# remap_2025-11-01.net
KiCad netlist of a schematic drawn in EasyEDA Pro
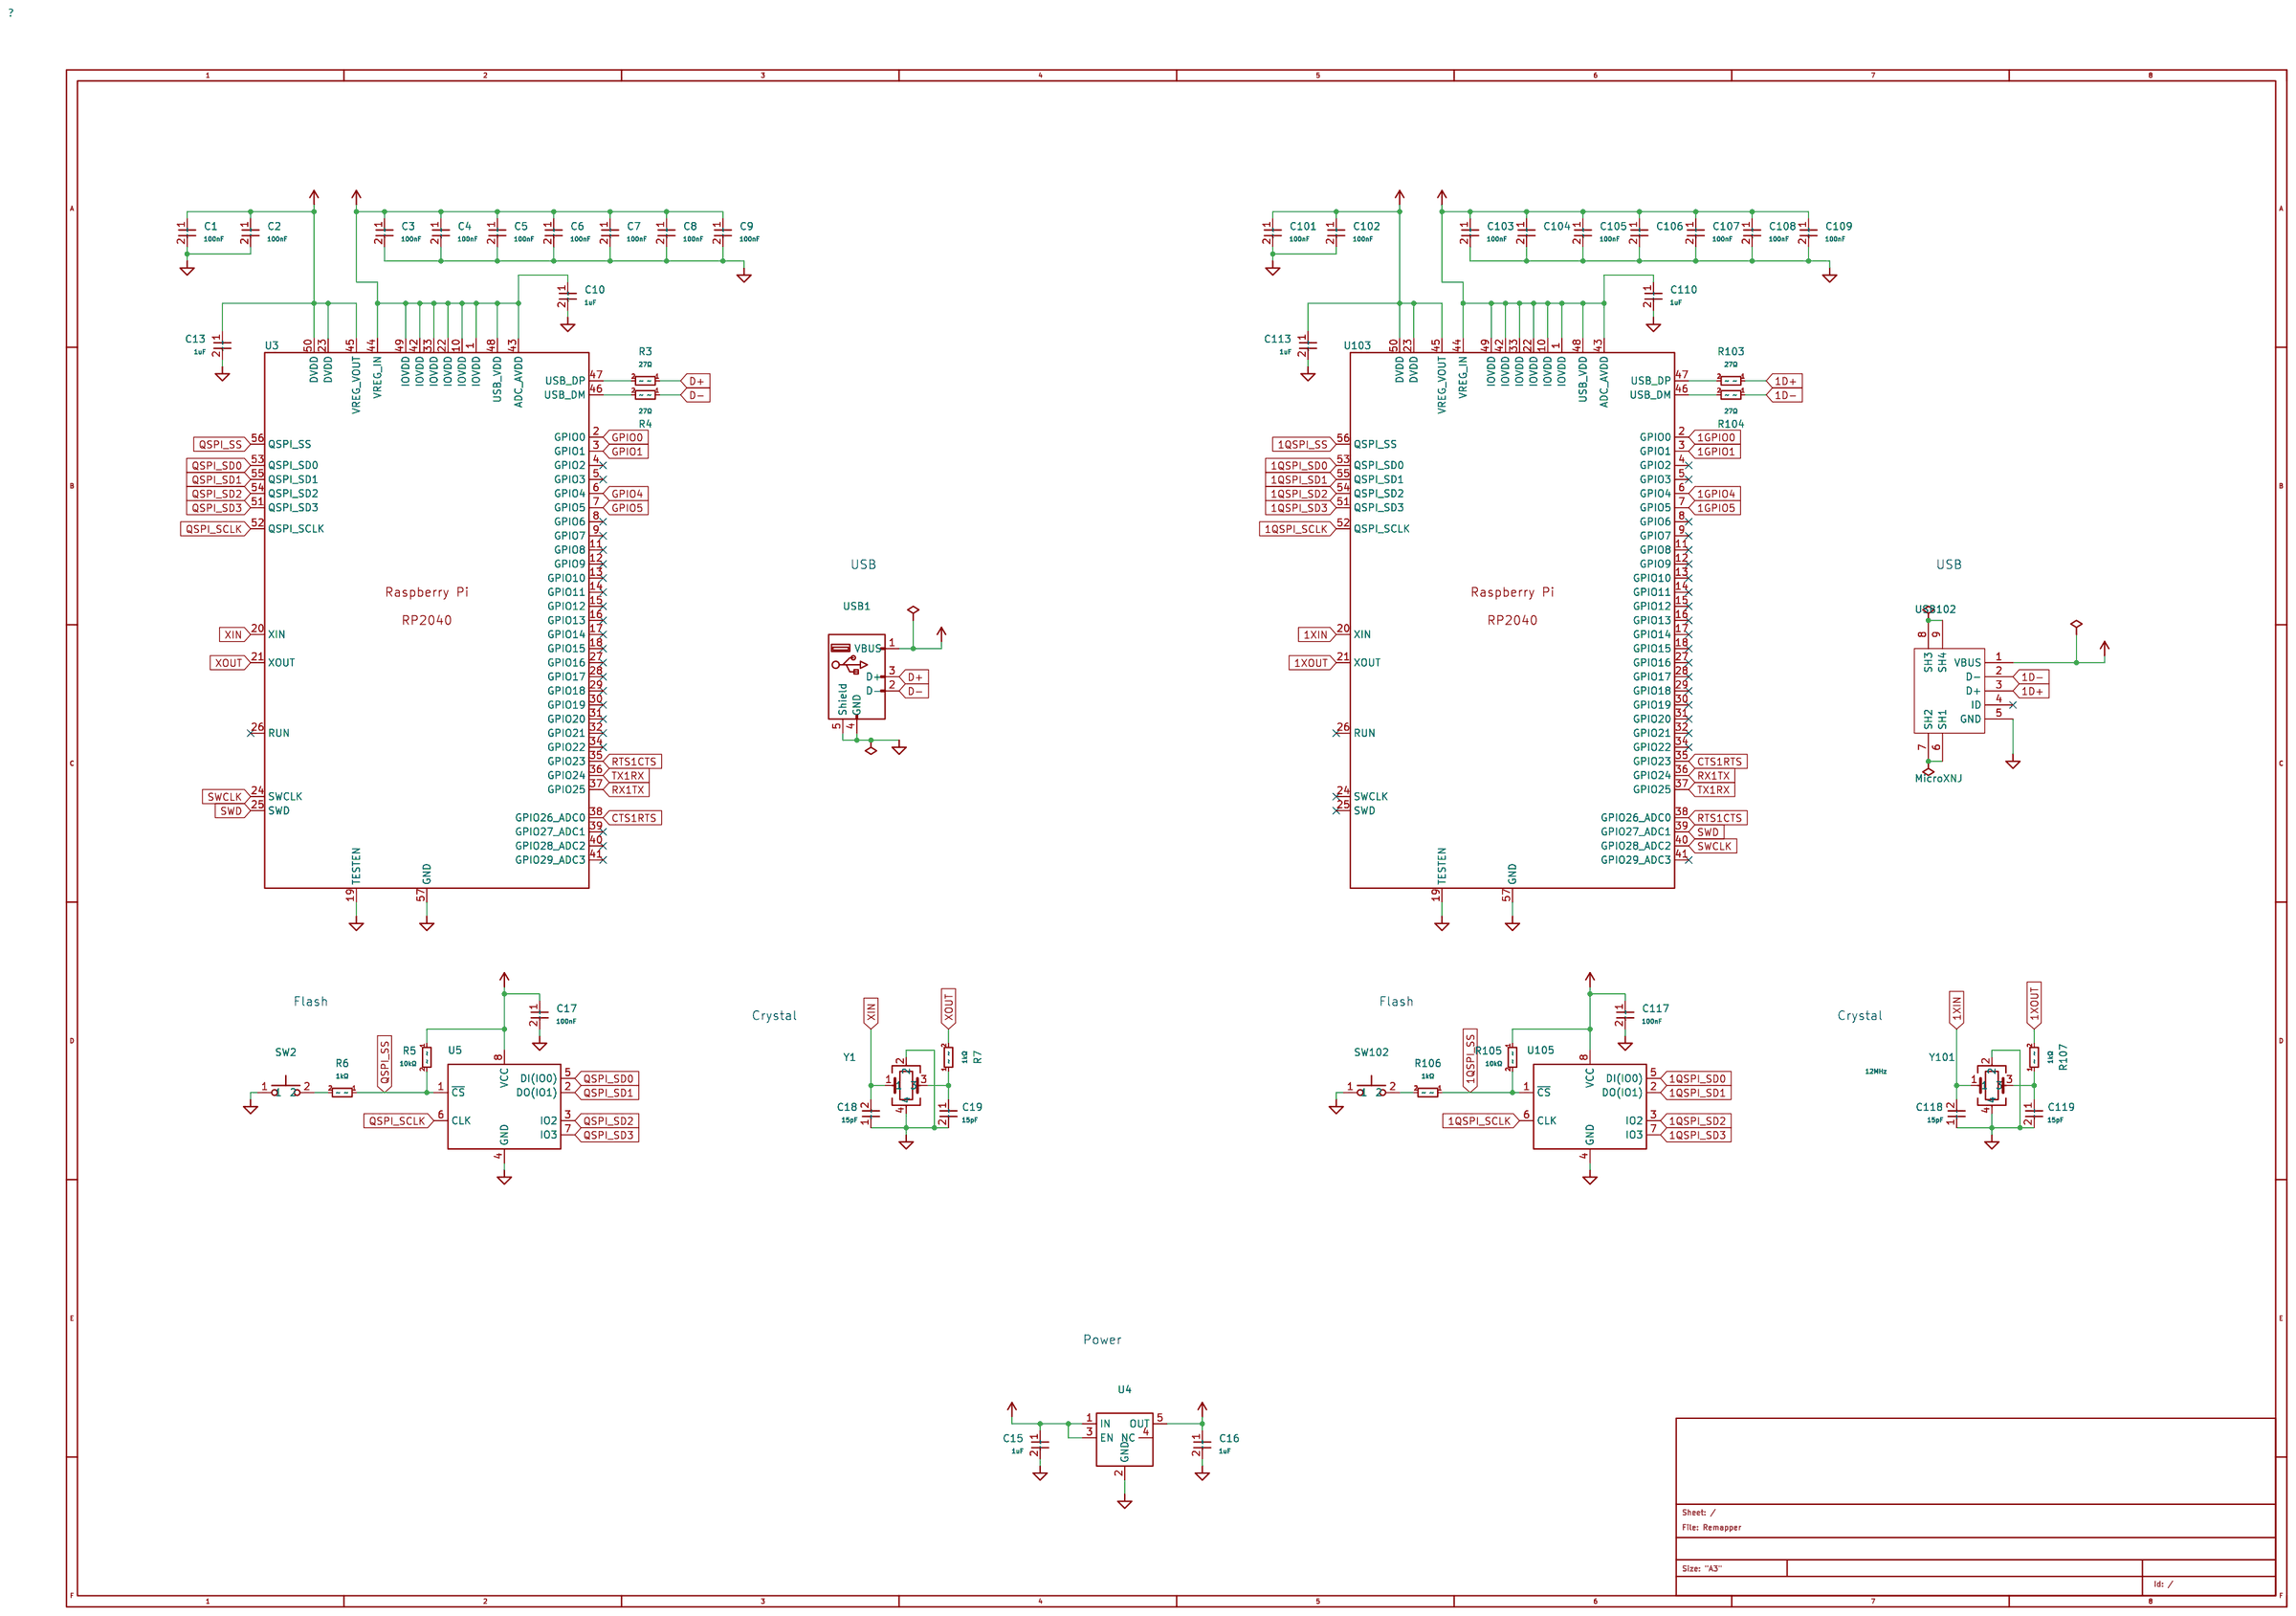
[diagram p0: schematic sheet]

(export (version "E")
  (design (tool "Eeschema 10.0.6"))
  (components
    (comp (ref "C1")
      (value "100nF")
      (description "Capacitance:100nF Tolerance:±10% Tolerance:±10% Voltage Rating:16V Temperature Coefficient:X7R")
      (fields
        (field (name "Manufacturer Part") "CL05B104KO5NNNC")
        (field (name "Manufacturer") "SAMSUNG(三星)")
      )
      (libsource (lib "easyedapro") (part "Device_C_Small"))
    )
    (comp (ref "C2")
      (value "100nF")
      (description "Capacitance:100nF Tolerance:±10% Tolerance:±10% Voltage Rating:16V Temperature Coefficient:X7R")
      (fields
        (field (name "Manufacturer Part") "CL05B104KO5NNNC")
        (field (name "Manufacturer") "SAMSUNG(三星)")
      )
      (libsource (lib "easyedapro") (part "Device_C_Small"))
    )
    (comp (ref "C3")
      (value "100nF")
      (description "Capacitance:100nF Tolerance:±10% Tolerance:±10% Voltage Rating:16V Temperature Coefficient:X7R")
      (fields
        (field (name "Manufacturer Part") "CL05B104KO5NNNC")
        (field (name "Manufacturer") "SAMSUNG(三星)")
      )
      (libsource (lib "easyedapro") (part "Device_C_Small"))
    )
    (comp (ref "C4")
      (value "100nF")
      (description "Capacitance:100nF Tolerance:±10% Tolerance:±10% Voltage Rating:16V Temperature Coefficient:X7R")
      (fields
        (field (name "Manufacturer Part") "CL05B104KO5NNNC")
        (field (name "Manufacturer") "SAMSUNG(三星)")
      )
      (libsource (lib "easyedapro") (part "Device_C_Small"))
    )
    (comp (ref "C5")
      (value "100nF")
      (description "Capacitance:100nF Tolerance:±10% Tolerance:±10% Voltage Rating:16V Temperature Coefficient:X7R")
      (fields
        (field (name "Manufacturer Part") "CL05B104KO5NNNC")
        (field (name "Manufacturer") "SAMSUNG(三星)")
      )
      (libsource (lib "easyedapro") (part "Device_C_Small"))
    )
    (comp (ref "C6")
      (value "100nF")
      (description "Capacitance:100nF Tolerance:±10% Tolerance:±10% Voltage Rating:16V Temperature Coefficient:X7R")
      (fields
        (field (name "Manufacturer Part") "CL05B104KO5NNNC")
        (field (name "Manufacturer") "SAMSUNG(三星)")
      )
      (libsource (lib "easyedapro") (part "Device_C_Small"))
    )
    (comp (ref "C7")
      (value "100nF")
      (description "Capacitance:100nF Tolerance:±10% Tolerance:±10% Voltage Rating:16V Temperature Coefficient:X7R")
      (fields
        (field (name "Manufacturer Part") "CL05B104KO5NNNC")
        (field (name "Manufacturer") "SAMSUNG(三星)")
      )
      (libsource (lib "easyedapro") (part "Device_C_Small"))
    )
    (comp (ref "C8")
      (value "100nF")
      (description "Capacitance:100nF Tolerance:±10% Tolerance:±10% Voltage Rating:16V Temperature Coefficient:X7R")
      (fields
        (field (name "Manufacturer Part") "CL05B104KO5NNNC")
        (field (name "Manufacturer") "SAMSUNG(三星)")
      )
      (libsource (lib "easyedapro") (part "Device_C_Small"))
    )
    (comp (ref "C9")
      (value "100nF")
      (description "Capacitance:100nF Tolerance:±10% Tolerance:±10% Voltage Rating:16V Temperature Coefficient:X7R")
      (fields
        (field (name "Manufacturer Part") "CL05B104KO5NNNC")
        (field (name "Manufacturer") "SAMSUNG(三星)")
      )
      (libsource (lib "easyedapro") (part "Device_C_Small"))
    )
    (comp (ref "C10")
      (value "1uF")
      (description "Capacitance:1uF Tolerance:±10% Tolerance:±10% Voltage Rating:25V Temperature Coefficient:X5R")
      (fields
        (field (name "Manufacturer Part") "CL05A105KA5NQNC")
        (field (name "Manufacturer") "SAMSUNG(三星)")
      )
      (libsource (lib "easyedapro") (part "Device_C_Small"))
    )
    (comp (ref "C13")
      (value "1uF")
      (description "Capacitance:1uF Tolerance:±10% Tolerance:±10% Voltage Rating:25V Temperature Coefficient:X5R")
      (fields
        (field (name "Manufacturer Part") "CL05A105KA5NQNC")
        (field (name "Manufacturer") "SAMSUNG(三星)")
      )
      (libsource (lib "easyedapro") (part "Device_C_Small"))
    )
    (comp (ref "C15")
      (value "1uF")
      (description "Capacitance:1uF Tolerance:±10% Tolerance:±10% Voltage Rating:25V Temperature Coefficient:X5R")
      (fields
        (field (name "Manufacturer Part") "CL05A105KA5NQNC")
        (field (name "Manufacturer") "SAMSUNG(三星)")
      )
      (libsource (lib "easyedapro") (part "Device_C_Small"))
    )
    (comp (ref "C16")
      (value "1uF")
      (description "Capacitance:1uF Tolerance:±10% Tolerance:±10% Voltage Rating:25V Temperature Coefficient:X5R")
      (fields
        (field (name "Manufacturer Part") "CL05A105KA5NQNC")
        (field (name "Manufacturer") "SAMSUNG(三星)")
      )
      (libsource (lib "easyedapro") (part "Device_C_Small"))
    )
    (comp (ref "C17")
      (value "100nF")
      (description "Capacitance:100nF Tolerance:±10% Tolerance:±10% Voltage Rating:16V Temperature Coefficient:X7R")
      (fields
        (field (name "Manufacturer Part") "CL05B104KO5NNNC")
        (field (name "Manufacturer") "SAMSUNG(三星)")
      )
      (libsource (lib "easyedapro") (part "Device_C_Small"))
    )
    (comp (ref "C18")
      (value "15pF")
      (description "Capacitance:15pF Tolerance:±5% Tolerance:±5% Voltage Rating:50V Temperature Coefficient:C0G")
      (fields (field (name "Manufacturer Part") "0402CG150J500NT") (field (name "Manufacturer") "FH(风华)"))
      (libsource (lib "easyedapro") (part "Device_C_Small"))
    )
    (comp (ref "C19")
      (value "15pF")
      (description "Capacitance:15pF Tolerance:±5% Tolerance:±5% Voltage Rating:50V Temperature Coefficient:C0G")
      (fields (field (name "Manufacturer Part") "0402CG150J500NT") (field (name "Manufacturer") "FH(风华)"))
      (libsource (lib "easyedapro") (part "Device_C_Small"))
    )
    (comp (ref "C101")
      (value "100nF")
      (description "Capacitance:100nF Tolerance:±10% Tolerance:±10% Voltage Rating:16V Temperature Coefficient:X7R")
      (fields
        (field (name "Manufacturer Part") "CL05B104KO5NNNC")
        (field (name "Manufacturer") "SAMSUNG(三星)")
      )
      (libsource (lib "easyedapro") (part "Device_C_Small"))
    )
    (comp (ref "C102")
      (value "100nF")
      (description "Capacitance:100nF Tolerance:±10% Tolerance:±10% Voltage Rating:16V Temperature Coefficient:X7R")
      (fields
        (field (name "Manufacturer Part") "CL05B104KO5NNNC")
        (field (name "Manufacturer") "SAMSUNG(三星)")
      )
      (libsource (lib "easyedapro") (part "Device_C_Small"))
    )
    (comp (ref "C103")
      (value "100nF")
      (description "Capacitance:100nF Tolerance:±10% Tolerance:±10% Voltage Rating:16V Temperature Coefficient:X7R")
      (fields
        (field (name "Manufacturer Part") "CL05B104KO5NNNC")
        (field (name "Manufacturer") "SAMSUNG(三星)")
      )
      (libsource (lib "easyedapro") (part "Device_C_Small"))
    )
    (comp (ref "C104")
      (value "100nF")
      (description "Capacitance:100nF Tolerance:±10% Tolerance:±10% Voltage Rating:16V Temperature Coefficient:X7R")
      (fields
        (field (name "Manufacturer Part") "CL05B104KO5NNNC")
        (field (name "Manufacturer") "SAMSUNG(三星)")
      )
      (libsource (lib "easyedapro") (part "Device_C_Small"))
    )
    (comp (ref "C105")
      (value "100nF")
      (description "Capacitance:100nF Tolerance:±10% Tolerance:±10% Voltage Rating:16V Temperature Coefficient:X7R")
      (fields
        (field (name "Manufacturer Part") "CL05B104KO5NNNC")
        (field (name "Manufacturer") "SAMSUNG(三星)")
      )
      (libsource (lib "easyedapro") (part "Device_C_Small"))
    )
    (comp (ref "C106")
      (value "100nF")
      (description "Capacitance:100nF Tolerance:±10% Tolerance:±10% Voltage Rating:16V Temperature Coefficient:X7R")
      (fields
        (field (name "Manufacturer Part") "CL05B104KO5NNNC")
        (field (name "Manufacturer") "SAMSUNG(三星)")
      )
      (libsource (lib "easyedapro") (part "Device_C_Small"))
    )
    (comp (ref "C107")
      (value "100nF")
      (description "Capacitance:100nF Tolerance:±10% Tolerance:±10% Voltage Rating:16V Temperature Coefficient:X7R")
      (fields
        (field (name "Manufacturer Part") "CL05B104KO5NNNC")
        (field (name "Manufacturer") "SAMSUNG(三星)")
      )
      (libsource (lib "easyedapro") (part "Device_C_Small"))
    )
    (comp (ref "C108")
      (value "100nF")
      (description "Capacitance:100nF Tolerance:±10% Tolerance:±10% Voltage Rating:16V Temperature Coefficient:X7R")
      (fields
        (field (name "Manufacturer Part") "CL05B104KO5NNNC")
        (field (name "Manufacturer") "SAMSUNG(三星)")
      )
      (libsource (lib "easyedapro") (part "Device_C_Small"))
    )
    (comp (ref "C109")
      (value "100nF")
      (description "Capacitance:100nF Tolerance:±10% Tolerance:±10% Voltage Rating:16V Temperature Coefficient:X7R")
      (fields
        (field (name "Manufacturer Part") "CL05B104KO5NNNC")
        (field (name "Manufacturer") "SAMSUNG(三星)")
      )
      (libsource (lib "easyedapro") (part "Device_C_Small"))
    )
    (comp (ref "C110")
      (value "1uF")
      (description "Capacitance:1uF Tolerance:±10% Tolerance:±10% Voltage Rating:25V Temperature Coefficient:X5R")
      (fields
        (field (name "Manufacturer Part") "CL05A105KA5NQNC")
        (field (name "Manufacturer") "SAMSUNG(三星)")
      )
      (libsource (lib "easyedapro") (part "Device_C_Small"))
    )
    (comp (ref "C113")
      (value "1uF")
      (description "Capacitance:1uF Tolerance:±10% Tolerance:±10% Voltage Rating:25V Temperature Coefficient:X5R")
      (fields
        (field (name "Manufacturer Part") "CL05A105KA5NQNC")
        (field (name "Manufacturer") "SAMSUNG(三星)")
      )
      (libsource (lib "easyedapro") (part "Device_C_Small"))
    )
    (comp (ref "C117")
      (value "100nF")
      (description "Capacitance:100nF Tolerance:±10% Tolerance:±10% Voltage Rating:16V Temperature Coefficient:X7R")
      (fields
        (field (name "Manufacturer Part") "CL05B104KO5NNNC")
        (field (name "Manufacturer") "SAMSUNG(三星)")
      )
      (libsource (lib "easyedapro") (part "Device_C_Small"))
    )
    (comp (ref "C118")
      (value "15pF")
      (description "Capacitance:15pF Tolerance:±5% Tolerance:±5% Voltage Rating:50V Temperature Coefficient:C0G")
      (fields (field (name "Manufacturer Part") "0402CG150J500NT") (field (name "Manufacturer") "FH(风华)"))
      (libsource (lib "easyedapro") (part "Device_C_Small"))
    )
    (comp (ref "C119")
      (value "15pF")
      (description "Capacitance:15pF Tolerance:±5% Tolerance:±5% Voltage Rating:50V Temperature Coefficient:C0G")
      (fields (field (name "Manufacturer Part") "0402CG150J500NT") (field (name "Manufacturer") "FH(风华)"))
      (libsource (lib "easyedapro") (part "Device_C_Small"))
    )
    (comp (ref "R3")
      (value "27Ω")
      (fields (field (name "Manufacturer Part") "RC0402FR-0727RL") (field (name "Manufacturer") "YAGEO(国巨)"))
      (libsource (lib "easyedapro") (part "Device_R_Small"))
    )
    (comp (ref "R4")
      (value "27Ω")
      (fields (field (name "Manufacturer Part") "RC0402FR-0727RL") (field (name "Manufacturer") "YAGEO(国巨)"))
      (libsource (lib "easyedapro") (part "Device_R_Small"))
    )
    (comp (ref "R5")
      (value "10kΩ")
      (fields
        (field (name "Manufacturer Part") "0402WGF1002TCE")
        (field (name "Manufacturer") "UNI-ROYAL(厚声)")
      )
      (libsource (lib "easyedapro") (part "Device_R_Small"))
    )
    (comp (ref "R6")
      (value "1kΩ")
      (fields
        (field (name "Manufacturer Part") "0402WGF1001TCE")
        (field (name "Manufacturer") "UNI-ROYAL(厚声)")
      )
      (libsource (lib "easyedapro") (part "Device_R_Small"))
    )
    (comp (ref "R7")
      (value "1kΩ")
      (fields
        (field (name "Manufacturer Part") "0402WGF1001TCE")
        (field (name "Manufacturer") "UNI-ROYAL(厚声)")
      )
      (libsource (lib "easyedapro") (part "Device_R_Small"))
    )
    (comp (ref "R103")
      (value "27Ω")
      (fields (field (name "Manufacturer Part") "RC0402FR-0727RL") (field (name "Manufacturer") "YAGEO(国巨)"))
      (libsource (lib "easyedapro") (part "Device_R_Small"))
    )
    (comp (ref "R104")
      (value "27Ω")
      (fields (field (name "Manufacturer Part") "RC0402FR-0727RL") (field (name "Manufacturer") "YAGEO(国巨)"))
      (libsource (lib "easyedapro") (part "Device_R_Small"))
    )
    (comp (ref "R105")
      (value "10kΩ")
      (fields
        (field (name "Manufacturer Part") "0402WGF1002TCE")
        (field (name "Manufacturer") "UNI-ROYAL(厚声)")
      )
      (libsource (lib "easyedapro") (part "Device_R_Small"))
    )
    (comp (ref "R106")
      (value "1kΩ")
      (fields
        (field (name "Manufacturer Part") "0402WGF1001TCE")
        (field (name "Manufacturer") "UNI-ROYAL(厚声)")
      )
      (libsource (lib "easyedapro") (part "Device_R_Small"))
    )
    (comp (ref "R107")
      (value "1kΩ")
      (fields
        (field (name "Manufacturer Part") "0402WGF1001TCE")
        (field (name "Manufacturer") "UNI-ROYAL(厚声)")
      )
      (libsource (lib "easyedapro") (part "Device_R_Small"))
    )
    (comp (ref "SW2")
      (value "B3U-1000P")
      (fields (field (name "Manufacturer") "OMRON(欧姆龙)"))
      (libsource (lib "easyedapro") (part "Switch_SW_Push"))
    )
    (comp (ref "SW102")
      (value "B3U-1000P")
      (fields (field (name "Manufacturer") "OMRON(欧姆龙)"))
      (libsource (lib "easyedapro") (part "Switch_SW_Push"))
    )
    (comp (ref "U3")
      (value "RP2040")
      (description "CPU Core:- CPU Maximum Speed:133MHz Number of I/O:30 ADC (Bit):12bit Applications:-")
      (fields (field (name "Manufacturer") "Raspberry Pi(树莓派)"))
      (libsource (lib "easyedapro") (part "RP2040_RP2040"))
    )
    (comp (ref "U4")
      (value "TLV73333PDBVR")
      (fields (field (name "Manufacturer") "TI(德州仪器)"))
      (libsource (lib "easyedapro") (part "Regulator_Linear_TLV73333PDBV"))
    )
    (comp (ref "U5")
      (value "W25Q16JVUXIQ")
      (fields (field (name "Manufacturer") "Winbond(华邦)"))
      (libsource (lib "easyedapro") (part "Memory_Flash_W25Q128JVS"))
    )
    (comp (ref "U103")
      (value "RP2040")
      (description "CPU Core:- CPU Maximum Speed:133MHz Number of I/O:30 ADC (Bit):12bit Applications:-")
      (fields (field (name "Manufacturer") "Raspberry Pi(树莓派)"))
      (libsource (lib "easyedapro") (part "RP2040_RP2040"))
    )
    (comp (ref "U105")
      (value "W25Q16JVUXIQ")
      (fields (field (name "Manufacturer") "Winbond(华邦)"))
      (libsource (lib "easyedapro") (part "Memory_Flash_W25Q128JVS"))
    )
    (comp (ref "USB1")
      (value "U-USBAR04P-F002")
      (fields (field (name "Manufacturer") "Ckmtw(灿科盟)"))
      (libsource (lib "easyedapro") (part "Connector_USB_A"))
    )
    (comp (ref "USB102")
      (value "MicroXNJ")
      (footprint "easyedapro:MICRO-USB-SMD_MICROXNJ")
      (fields (field (name "Manufacturer") "SHOU HAN(首韩)"))
      (libsource (lib "easyedapro") (part "MICROXNJ"))
    )
    (comp (ref "Y1")
      (value "12MHz")
      (fields (field (name "Manufacturer Part") "X252012MMB4SI-24") (field (name "Manufacturer") "YXC(扬兴晶振)"))
      (libsource (lib "easyedapro") (part "Device_Crystal_GND24"))
    )
    (comp (ref "Y101")
      (value "12MHz")
      (fields (field (name "Manufacturer Part") "X252012MMB4SI-24") (field (name "Manufacturer") "YXC(扬兴晶振)"))
      (libsource (lib "easyedapro") (part "Device_Crystal_GND24"))
    )
  )
  (nets
    (net (code "1") (name "+1V1") (class "Default")
      (node (ref "C1") (pin "1") (pinfunction "~_1") (pintype "unspecified"))
      (node (ref "C13") (pin "1") (pinfunction "~_1") (pintype "unspecified"))
      (node (ref "C2") (pin "1") (pinfunction "~_1") (pintype "unspecified"))
      (node (ref "U3") (pin "23") (pinfunction "DVDD_23") (pintype "unspecified"))
      (node (ref "U3") (pin "45") (pinfunction "VREG_VOUT_45") (pintype "unspecified"))
      (node (ref "U3") (pin "50") (pinfunction "DVDD_50") (pintype "unspecified"))
    )
    (net (code "2") (name "+1V2") (class "Default")
      (node (ref "C101") (pin "1") (pinfunction "~_1") (pintype "unspecified"))
      (node (ref "C102") (pin "1") (pinfunction "~_1") (pintype "unspecified"))
      (node (ref "C113") (pin "1") (pinfunction "~_1") (pintype "unspecified"))
      (node (ref "U103") (pin "23") (pinfunction "DVDD_23") (pintype "unspecified"))
      (node (ref "U103") (pin "45") (pinfunction "VREG_VOUT_45") (pintype "unspecified"))
      (node (ref "U103") (pin "50") (pinfunction "DVDD_50") (pintype "unspecified"))
    )
    (net (code "3") (name "+3V3") (class "Default")
      (node (ref "C10") (pin "1") (pinfunction "~_1") (pintype "unspecified"))
      (node (ref "C103") (pin "1") (pinfunction "~_1") (pintype "unspecified"))
      (node (ref "C104") (pin "1") (pinfunction "~_1") (pintype "unspecified"))
      (node (ref "C105") (pin "1") (pinfunction "~_1") (pintype "unspecified"))
      (node (ref "C106") (pin "1") (pinfunction "~_1") (pintype "unspecified"))
      (node (ref "C107") (pin "1") (pinfunction "~_1") (pintype "unspecified"))
      (node (ref "C108") (pin "1") (pinfunction "~_1") (pintype "unspecified"))
      (node (ref "C109") (pin "1") (pinfunction "~_1") (pintype "unspecified"))
      (node (ref "C110") (pin "1") (pinfunction "~_1") (pintype "unspecified"))
      (node (ref "C117") (pin "1") (pinfunction "~_1") (pintype "unspecified"))
      (node (ref "C16") (pin "1") (pinfunction "~_1") (pintype "unspecified"))
      (node (ref "C17") (pin "1") (pinfunction "~_1") (pintype "unspecified"))
      (node (ref "C3") (pin "1") (pinfunction "~_1") (pintype "unspecified"))
      (node (ref "C4") (pin "1") (pinfunction "~_1") (pintype "unspecified"))
      (node (ref "C5") (pin "1") (pinfunction "~_1") (pintype "unspecified"))
      (node (ref "C6") (pin "1") (pinfunction "~_1") (pintype "unspecified"))
      (node (ref "C7") (pin "1") (pinfunction "~_1") (pintype "unspecified"))
      (node (ref "C8") (pin "1") (pinfunction "~_1") (pintype "unspecified"))
      (node (ref "C9") (pin "1") (pinfunction "~_1") (pintype "unspecified"))
      (node (ref "R105") (pin "1") (pinfunction "~_1") (pintype "unspecified"))
      (node (ref "R5") (pin "1") (pinfunction "~_1") (pintype "unspecified"))
      (node (ref "U103") (pin "1") (pinfunction "IOVDD_1") (pintype "unspecified"))
      (node (ref "U103") (pin "10") (pinfunction "IOVDD_10") (pintype "unspecified"))
      (node (ref "U103") (pin "22") (pinfunction "IOVDD_22") (pintype "unspecified"))
      (node (ref "U103") (pin "33") (pinfunction "IOVDD_33") (pintype "unspecified"))
      (node (ref "U103") (pin "42") (pinfunction "IOVDD_42") (pintype "unspecified"))
      (node (ref "U103") (pin "43") (pinfunction "ADC_AVDD_43") (pintype "unspecified"))
      (node (ref "U103") (pin "44") (pinfunction "VREG_IN_44") (pintype "unspecified"))
      (node (ref "U103") (pin "48") (pinfunction "USB_VDD_48") (pintype "unspecified"))
      (node (ref "U103") (pin "49") (pinfunction "IOVDD_49") (pintype "unspecified"))
      (node (ref "U105") (pin "8") (pinfunction "VCC_8") (pintype "unspecified"))
      (node (ref "U3") (pin "1") (pinfunction "IOVDD_1") (pintype "unspecified"))
      (node (ref "U3") (pin "10") (pinfunction "IOVDD_10") (pintype "unspecified"))
      (node (ref "U3") (pin "22") (pinfunction "IOVDD_22") (pintype "unspecified"))
      (node (ref "U3") (pin "33") (pinfunction "IOVDD_33") (pintype "unspecified"))
      (node (ref "U3") (pin "42") (pinfunction "IOVDD_42") (pintype "unspecified"))
      (node (ref "U3") (pin "43") (pinfunction "ADC_AVDD_43") (pintype "unspecified"))
      (node (ref "U3") (pin "44") (pinfunction "VREG_IN_44") (pintype "unspecified"))
      (node (ref "U3") (pin "48") (pinfunction "USB_VDD_48") (pintype "unspecified"))
      (node (ref "U3") (pin "49") (pinfunction "IOVDD_49") (pintype "unspecified"))
      (node (ref "U4") (pin "5") (pinfunction "OUT_5") (pintype "unspecified"))
      (node (ref "U5") (pin "8") (pinfunction "VCC_8") (pintype "unspecified"))
    )
    (net (code "4") (name "+5V") (class "Default")
      (node (ref "C15") (pin "1") (pinfunction "~_1") (pintype "unspecified"))
      (node (ref "U4") (pin "1") (pinfunction "IN_1") (pintype "unspecified"))
      (node (ref "U4") (pin "3") (pinfunction "EN_3") (pintype "input"))
      (node (ref "USB1") (pin "1") (pinfunction "VBUS_1") (pintype "unspecified"))
      (node (ref "USB102") (pin "1") (pinfunction "VBUS_1") (pintype "unspecified"))
    )
    (net (code "5") (name "1D+") (class "Default")
      (node (ref "R103") (pin "1") (pinfunction "~_1") (pintype "unspecified"))
      (node (ref "USB102") (pin "3") (pinfunction "D+_3") (pintype "unspecified"))
    )
    (net (code "6") (name "1D-") (class "Default")
      (node (ref "R104") (pin "1") (pinfunction "~_1") (pintype "unspecified"))
      (node (ref "USB102") (pin "2") (pinfunction "D-_2") (pintype "unspecified"))
    )
    (net (code "7") (name "1GPIO0") (class "Default")
      (node (ref "U103") (pin "2") (pinfunction "GPIO0_2") (pintype "bidirectional"))
    )
    (net (code "8") (name "1GPIO1") (class "Default")
      (node (ref "U103") (pin "3") (pinfunction "GPIO1_3") (pintype "bidirectional"))
    )
    (net (code "9") (name "1GPIO4") (class "Default")
      (node (ref "U103") (pin "6") (pinfunction "GPIO4_6") (pintype "bidirectional"))
    )
    (net (code "10") (name "1GPIO5") (class "Default")
      (node (ref "U103") (pin "7") (pinfunction "GPIO5_7") (pintype "bidirectional"))
    )
    (net (code "11") (name "1QSPI_SCLK") (class "Default")
      (node (ref "U103") (pin "52") (pinfunction "QSPI_SCLK_52") (pintype "output"))
      (node (ref "U105") (pin "6") (pinfunction "CLK_6") (pintype "input"))
    )
    (net (code "12") (name "1QSPI_SD0") (class "Default")
      (node (ref "U103") (pin "53") (pinfunction "QSPI_SD0_53") (pintype "bidirectional"))
      (node (ref "U105") (pin "5") (pinfunction "DI(IO0)_5") (pintype "bidirectional"))
    )
    (net (code "13") (name "1QSPI_SD1") (class "Default")
      (node (ref "U103") (pin "55") (pinfunction "QSPI_SD1_55") (pintype "bidirectional"))
      (node (ref "U105") (pin "2") (pinfunction "DO(IO1)_2") (pintype "bidirectional"))
    )
    (net (code "14") (name "1QSPI_SD2") (class "Default")
      (node (ref "U103") (pin "54") (pinfunction "QSPI_SD2_54") (pintype "bidirectional"))
      (node (ref "U105") (pin "3") (pinfunction "IO2_3") (pintype "bidirectional"))
    )
    (net (code "15") (name "1QSPI_SD3") (class "Default")
      (node (ref "U103") (pin "51") (pinfunction "QSPI_SD3_51") (pintype "bidirectional"))
      (node (ref "U105") (pin "7") (pinfunction "IO3_7") (pintype "bidirectional"))
    )
    (net (code "16") (name "1QSPI_SS") (class "Default")
      (node (ref "R105") (pin "2") (pinfunction "~_2") (pintype "unspecified"))
      (node (ref "R106") (pin "1") (pinfunction "~_1") (pintype "unspecified"))
      (node (ref "U103") (pin "56") (pinfunction "QSPI_SS_56") (pintype "bidirectional"))
      (node (ref "U105") (pin "1") (pinfunction "~{CS}_1") (pintype "input"))
    )
    (net (code "17") (name "1XIN") (class "Default")
      (node (ref "C118") (pin "2") (pinfunction "~_2") (pintype "unspecified"))
      (node (ref "U103") (pin "20") (pinfunction "XIN_20") (pintype "input"))
      (node (ref "Y101") (pin "1") (pinfunction "1_1") (pintype "unspecified"))
    )
    (net (code "18") (name "1XOUT") (class "Default")
      (node (ref "R107") (pin "2") (pinfunction "~_2") (pintype "unspecified"))
      (node (ref "U103") (pin "21") (pinfunction "XOUT_21") (pintype "unspecified"))
    )
    (net (code "19") (name "CTS1RTS") (class "Default")
      (node (ref "U103") (pin "35") (pinfunction "GPIO23_35") (pintype "bidirectional"))
      (node (ref "U3") (pin "38") (pinfunction "GPIO26_ADC0_38") (pintype "bidirectional"))
    )
    (net (code "20") (name "D+") (class "Default")
      (node (ref "R3") (pin "1") (pinfunction "~_1") (pintype "unspecified"))
      (node (ref "USB1") (pin "3") (pinfunction "D+_3") (pintype "bidirectional"))
    )
    (net (code "21") (name "D-") (class "Default")
      (node (ref "R4") (pin "1") (pinfunction "~_1") (pintype "unspecified"))
      (node (ref "USB1") (pin "2") (pinfunction "D-_2") (pintype "bidirectional"))
    )
    (net (code "22") (name "GND") (class "Default")
      (node (ref "C1") (pin "2") (pinfunction "~_2") (pintype "unspecified"))
      (node (ref "C10") (pin "2") (pinfunction "~_2") (pintype "unspecified"))
      (node (ref "C101") (pin "2") (pinfunction "~_2") (pintype "unspecified"))
      (node (ref "C102") (pin "2") (pinfunction "~_2") (pintype "unspecified"))
      (node (ref "C103") (pin "2") (pinfunction "~_2") (pintype "unspecified"))
      (node (ref "C104") (pin "2") (pinfunction "~_2") (pintype "unspecified"))
      (node (ref "C105") (pin "2") (pinfunction "~_2") (pintype "unspecified"))
      (node (ref "C106") (pin "2") (pinfunction "~_2") (pintype "unspecified"))
      (node (ref "C107") (pin "2") (pinfunction "~_2") (pintype "unspecified"))
      (node (ref "C108") (pin "2") (pinfunction "~_2") (pintype "unspecified"))
      (node (ref "C109") (pin "2") (pinfunction "~_2") (pintype "unspecified"))
      (node (ref "C110") (pin "2") (pinfunction "~_2") (pintype "unspecified"))
      (node (ref "C113") (pin "2") (pinfunction "~_2") (pintype "unspecified"))
      (node (ref "C117") (pin "2") (pinfunction "~_2") (pintype "unspecified"))
      (node (ref "C118") (pin "1") (pinfunction "~_1") (pintype "unspecified"))
      (node (ref "C119") (pin "2") (pinfunction "~_2") (pintype "unspecified"))
      (node (ref "C13") (pin "2") (pinfunction "~_2") (pintype "unspecified"))
      (node (ref "C15") (pin "2") (pinfunction "~_2") (pintype "unspecified"))
      (node (ref "C16") (pin "2") (pinfunction "~_2") (pintype "unspecified"))
      (node (ref "C17") (pin "2") (pinfunction "~_2") (pintype "unspecified"))
      (node (ref "C18") (pin "1") (pinfunction "~_1") (pintype "unspecified"))
      (node (ref "C19") (pin "2") (pinfunction "~_2") (pintype "unspecified"))
      (node (ref "C2") (pin "2") (pinfunction "~_2") (pintype "unspecified"))
      (node (ref "C3") (pin "2") (pinfunction "~_2") (pintype "unspecified"))
      (node (ref "C4") (pin "2") (pinfunction "~_2") (pintype "unspecified"))
      (node (ref "C5") (pin "2") (pinfunction "~_2") (pintype "unspecified"))
      (node (ref "C6") (pin "2") (pinfunction "~_2") (pintype "unspecified"))
      (node (ref "C7") (pin "2") (pinfunction "~_2") (pintype "unspecified"))
      (node (ref "C8") (pin "2") (pinfunction "~_2") (pintype "unspecified"))
      (node (ref "C9") (pin "2") (pinfunction "~_2") (pintype "unspecified"))
      (node (ref "SW102") (pin "1") (pinfunction "1_1") (pintype "unspecified"))
      (node (ref "SW2") (pin "1") (pinfunction "1_1") (pintype "unspecified"))
      (node (ref "U103") (pin "19") (pinfunction "TESTEN_19") (pintype "unspecified"))
      (node (ref "U103") (pin "57") (pinfunction "GND_57") (pintype "unspecified"))
      (node (ref "U105") (pin "4") (pinfunction "GND_4") (pintype "unspecified"))
      (node (ref "U3") (pin "19") (pinfunction "TESTEN_19") (pintype "unspecified"))
      (node (ref "U3") (pin "57") (pinfunction "GND_57") (pintype "unspecified"))
      (node (ref "U4") (pin "2") (pinfunction "GND_2") (pintype "unspecified"))
      (node (ref "U5") (pin "4") (pinfunction "GND_4") (pintype "unspecified"))
      (node (ref "USB1") (pin "4") (pinfunction "GND_4") (pintype "unspecified"))
      (node (ref "USB1") (pin "5") (pinfunction "Shield_5") (pintype "unspecified"))
      (node (ref "USB102") (pin "5") (pinfunction "GND_5") (pintype "unspecified"))
      (node (ref "USB102") (pin "6") (pinfunction "SH1_6") (pintype "unspecified"))
      (node (ref "USB102") (pin "7") (pinfunction "SH2_7") (pintype "unspecified"))
      (node (ref "USB102") (pin "8") (pinfunction "SH3_8") (pintype "unspecified"))
      (node (ref "USB102") (pin "9") (pinfunction "SH4_9") (pintype "unspecified"))
      (node (ref "Y1") (pin "2") (pinfunction "2_2") (pintype "unspecified"))
      (node (ref "Y1") (pin "4") (pinfunction "4_4") (pintype "unspecified"))
      (node (ref "Y101") (pin "2") (pinfunction "2_2") (pintype "unspecified"))
      (node (ref "Y101") (pin "4") (pinfunction "4_4") (pintype "unspecified"))
    )
    (net (code "23") (name "GPIO0") (class "Default")
      (node (ref "U3") (pin "2") (pinfunction "GPIO0_2") (pintype "bidirectional"))
    )
    (net (code "24") (name "GPIO1") (class "Default")
      (node (ref "U3") (pin "3") (pinfunction "GPIO1_3") (pintype "bidirectional"))
    )
    (net (code "25") (name "GPIO4") (class "Default")
      (node (ref "U3") (pin "6") (pinfunction "GPIO4_6") (pintype "bidirectional"))
    )
    (net (code "26") (name "GPIO5") (class "Default")
      (node (ref "U3") (pin "7") (pinfunction "GPIO5_7") (pintype "bidirectional"))
    )
    (net (code "27") (name "Net-(C19-~-Pad1)") (class "Default")
      (node (ref "C19") (pin "1") (pinfunction "~_1") (pintype "unspecified"))
      (node (ref "R7") (pin "1") (pinfunction "~_1") (pintype "unspecified"))
      (node (ref "Y1") (pin "3") (pinfunction "3_3") (pintype "unspecified"))
    )
    (net (code "28") (name "Net-(C119-~-Pad1)") (class "Default")
      (node (ref "C119") (pin "1") (pinfunction "~_1") (pintype "unspecified"))
      (node (ref "R107") (pin "1") (pinfunction "~_1") (pintype "unspecified"))
      (node (ref "Y101") (pin "3") (pinfunction "3_3") (pintype "unspecified"))
    )
    (net (code "29") (name "Net-(R6-~-Pad2)") (class "Default")
      (node (ref "R6") (pin "2") (pinfunction "~_2") (pintype "unspecified"))
      (node (ref "SW2") (pin "2") (pinfunction "2_2") (pintype "unspecified"))
    )
    (net (code "30") (name "Net-(R106-~-Pad2)") (class "Default")
      (node (ref "R106") (pin "2") (pinfunction "~_2") (pintype "unspecified"))
      (node (ref "SW102") (pin "2") (pinfunction "2_2") (pintype "unspecified"))
    )
    (net (code "31") (name "Net-(U3-USB_DM)") (class "Default")
      (node (ref "R4") (pin "2") (pinfunction "~_2") (pintype "unspecified"))
      (node (ref "U3") (pin "46") (pinfunction "USB_DM_46") (pintype "bidirectional"))
    )
    (net (code "32") (name "Net-(U3-USB_DP)") (class "Default")
      (node (ref "R3") (pin "2") (pinfunction "~_2") (pintype "unspecified"))
      (node (ref "U3") (pin "47") (pinfunction "USB_DP_47") (pintype "bidirectional"))
    )
    (net (code "33") (name "Net-(U103-USB_DM)") (class "Default")
      (node (ref "R104") (pin "2") (pinfunction "~_2") (pintype "unspecified"))
      (node (ref "U103") (pin "46") (pinfunction "USB_DM_46") (pintype "bidirectional"))
    )
    (net (code "34") (name "Net-(U103-USB_DP)") (class "Default")
      (node (ref "R103") (pin "2") (pinfunction "~_2") (pintype "unspecified"))
      (node (ref "U103") (pin "47") (pinfunction "USB_DP_47") (pintype "bidirectional"))
    )
    (net (code "35") (name "QSPI_SCLK") (class "Default")
      (node (ref "U3") (pin "52") (pinfunction "QSPI_SCLK_52") (pintype "output"))
      (node (ref "U5") (pin "6") (pinfunction "CLK_6") (pintype "input"))
    )
    (net (code "36") (name "QSPI_SD0") (class "Default")
      (node (ref "U3") (pin "53") (pinfunction "QSPI_SD0_53") (pintype "bidirectional"))
      (node (ref "U5") (pin "5") (pinfunction "DI(IO0)_5") (pintype "bidirectional"))
    )
    (net (code "37") (name "QSPI_SD1") (class "Default")
      (node (ref "U3") (pin "55") (pinfunction "QSPI_SD1_55") (pintype "bidirectional"))
      (node (ref "U5") (pin "2") (pinfunction "DO(IO1)_2") (pintype "bidirectional"))
    )
    (net (code "38") (name "QSPI_SD2") (class "Default")
      (node (ref "U3") (pin "54") (pinfunction "QSPI_SD2_54") (pintype "bidirectional"))
      (node (ref "U5") (pin "3") (pinfunction "IO2_3") (pintype "bidirectional"))
    )
    (net (code "39") (name "QSPI_SD3") (class "Default")
      (node (ref "U3") (pin "51") (pinfunction "QSPI_SD3_51") (pintype "bidirectional"))
      (node (ref "U5") (pin "7") (pinfunction "IO3_7") (pintype "bidirectional"))
    )
    (net (code "40") (name "QSPI_SS") (class "Default")
      (node (ref "R5") (pin "2") (pinfunction "~_2") (pintype "unspecified"))
      (node (ref "R6") (pin "1") (pinfunction "~_1") (pintype "unspecified"))
      (node (ref "U3") (pin "56") (pinfunction "QSPI_SS_56") (pintype "bidirectional"))
      (node (ref "U5") (pin "1") (pinfunction "~{CS}_1") (pintype "input"))
    )
    (net (code "41") (name "RTS1CTS") (class "Default")
      (node (ref "U103") (pin "38") (pinfunction "GPIO26_ADC0_38") (pintype "bidirectional"))
      (node (ref "U3") (pin "35") (pinfunction "GPIO23_35") (pintype "bidirectional"))
    )
    (net (code "42") (name "RX1TX") (class "Default")
      (node (ref "U103") (pin "36") (pinfunction "GPIO24_36") (pintype "bidirectional"))
      (node (ref "U3") (pin "37") (pinfunction "GPIO25_37") (pintype "bidirectional"))
    )
    (net (code "43") (name "SWCLK") (class "Default")
      (node (ref "U103") (pin "40") (pinfunction "GPIO28_ADC2_40") (pintype "bidirectional"))
      (node (ref "U3") (pin "24") (pinfunction "SWCLK_24") (pintype "output"))
    )
    (net (code "44") (name "SWD") (class "Default")
      (node (ref "U103") (pin "39") (pinfunction "GPIO27_ADC1_39") (pintype "bidirectional"))
      (node (ref "U3") (pin "25") (pinfunction "SWD_25") (pintype "bidirectional"))
    )
    (net (code "45") (name "TX1RX") (class "Default")
      (node (ref "U103") (pin "37") (pinfunction "GPIO25_37") (pintype "bidirectional"))
      (node (ref "U3") (pin "36") (pinfunction "GPIO24_36") (pintype "bidirectional"))
    )
    (net (code "46") (name "XIN") (class "Default")
      (node (ref "C18") (pin "2") (pinfunction "~_2") (pintype "unspecified"))
      (node (ref "U3") (pin "20") (pinfunction "XIN_20") (pintype "input"))
      (node (ref "Y1") (pin "1") (pinfunction "1_1") (pintype "unspecified"))
    )
    (net (code "47") (name "XOUT") (class "Default")
      (node (ref "R7") (pin "2") (pinfunction "~_2") (pintype "unspecified"))
      (node (ref "U3") (pin "21") (pinfunction "XOUT_21") (pintype "unspecified"))
    )
    (net (code "48") (name "unconnected-(U3-GPIO2-Pad4)") (class "Default")
      (node (ref "U3") (pin "4") (pinfunction "GPIO2_4") (pintype "bidirectional+no_connect"))
    )
    (net (code "49") (name "unconnected-(U3-GPIO3-Pad5)") (class "Default")
      (node (ref "U3") (pin "5") (pinfunction "GPIO3_5") (pintype "bidirectional+no_connect"))
    )
    (net (code "50") (name "unconnected-(U3-GPIO6-Pad8)") (class "Default")
      (node (ref "U3") (pin "8") (pinfunction "GPIO6_8") (pintype "bidirectional+no_connect"))
    )
    (net (code "51") (name "unconnected-(U3-GPIO7-Pad9)") (class "Default")
      (node (ref "U3") (pin "9") (pinfunction "GPIO7_9") (pintype "bidirectional+no_connect"))
    )
    (net (code "52") (name "unconnected-(U3-GPIO8-Pad11)") (class "Default")
      (node (ref "U3") (pin "11") (pinfunction "GPIO8_11") (pintype "bidirectional+no_connect"))
    )
    (net (code "53") (name "unconnected-(U3-GPIO9-Pad12)") (class "Default")
      (node (ref "U3") (pin "12") (pinfunction "GPIO9_12") (pintype "bidirectional+no_connect"))
    )
    (net (code "54") (name "unconnected-(U3-GPIO10-Pad13)") (class "Default")
      (node (ref "U3") (pin "13") (pinfunction "GPIO10_13") (pintype "bidirectional+no_connect"))
    )
    (net (code "55") (name "unconnected-(U3-GPIO11-Pad14)") (class "Default")
      (node (ref "U3") (pin "14") (pinfunction "GPIO11_14") (pintype "bidirectional+no_connect"))
    )
    (net (code "56") (name "unconnected-(U3-GPIO12-Pad15)") (class "Default")
      (node (ref "U3") (pin "15") (pinfunction "GPIO12_15") (pintype "bidirectional+no_connect"))
    )
    (net (code "57") (name "unconnected-(U3-GPIO13-Pad16)") (class "Default")
      (node (ref "U3") (pin "16") (pinfunction "GPIO13_16") (pintype "bidirectional+no_connect"))
    )
    (net (code "58") (name "unconnected-(U3-GPIO14-Pad17)") (class "Default")
      (node (ref "U3") (pin "17") (pinfunction "GPIO14_17") (pintype "bidirectional+no_connect"))
    )
    (net (code "59") (name "unconnected-(U3-GPIO15-Pad18)") (class "Default")
      (node (ref "U3") (pin "18") (pinfunction "GPIO15_18") (pintype "bidirectional+no_connect"))
    )
    (net (code "60") (name "unconnected-(U3-GPIO16-Pad27)") (class "Default")
      (node (ref "U3") (pin "27") (pinfunction "GPIO16_27") (pintype "bidirectional+no_connect"))
    )
    (net (code "61") (name "unconnected-(U3-GPIO17-Pad28)") (class "Default")
      (node (ref "U3") (pin "28") (pinfunction "GPIO17_28") (pintype "bidirectional+no_connect"))
    )
    (net (code "62") (name "unconnected-(U3-GPIO18-Pad29)") (class "Default")
      (node (ref "U3") (pin "29") (pinfunction "GPIO18_29") (pintype "bidirectional+no_connect"))
    )
    (net (code "63") (name "unconnected-(U3-GPIO19-Pad30)") (class "Default")
      (node (ref "U3") (pin "30") (pinfunction "GPIO19_30") (pintype "bidirectional+no_connect"))
    )
    (net (code "64") (name "unconnected-(U3-GPIO20-Pad31)") (class "Default")
      (node (ref "U3") (pin "31") (pinfunction "GPIO20_31") (pintype "bidirectional+no_connect"))
    )
    (net (code "65") (name "unconnected-(U3-GPIO21-Pad32)") (class "Default")
      (node (ref "U3") (pin "32") (pinfunction "GPIO21_32") (pintype "bidirectional+no_connect"))
    )
    (net (code "66") (name "unconnected-(U3-GPIO22-Pad34)") (class "Default")
      (node (ref "U3") (pin "34") (pinfunction "GPIO22_34") (pintype "bidirectional+no_connect"))
    )
    (net (code "67") (name "unconnected-(U3-GPIO27_ADC1-Pad39)") (class "Default")
      (node (ref "U3") (pin "39") (pinfunction "GPIO27_ADC1_39") (pintype "bidirectional+no_connect"))
    )
    (net (code "68") (name "unconnected-(U3-GPIO28_ADC2-Pad40)") (class "Default")
      (node (ref "U3") (pin "40") (pinfunction "GPIO28_ADC2_40") (pintype "bidirectional+no_connect"))
    )
    (net (code "69") (name "unconnected-(U3-GPIO29_ADC3-Pad41)") (class "Default")
      (node (ref "U3") (pin "41") (pinfunction "GPIO29_ADC3_41") (pintype "bidirectional+no_connect"))
    )
    (net (code "70") (name "unconnected-(U3-RUN-Pad26)") (class "Default")
      (node (ref "U3") (pin "26") (pinfunction "RUN_26") (pintype "input+no_connect"))
    )
    (net (code "71") (name "unconnected-(U4-NC-Pad4)") (class "Default")
      (node (ref "U4") (pin "4") (pinfunction "NC_4") (pintype "unspecified"))
    )
    (net (code "72") (name "unconnected-(U103-GPIO2-Pad4)") (class "Default")
      (node (ref "U103") (pin "4") (pinfunction "GPIO2_4") (pintype "bidirectional+no_connect"))
    )
    (net (code "73") (name "unconnected-(U103-GPIO3-Pad5)") (class "Default")
      (node (ref "U103") (pin "5") (pinfunction "GPIO3_5") (pintype "bidirectional+no_connect"))
    )
    (net (code "74") (name "unconnected-(U103-GPIO6-Pad8)") (class "Default")
      (node (ref "U103") (pin "8") (pinfunction "GPIO6_8") (pintype "bidirectional+no_connect"))
    )
    (net (code "75") (name "unconnected-(U103-GPIO7-Pad9)") (class "Default")
      (node (ref "U103") (pin "9") (pinfunction "GPIO7_9") (pintype "bidirectional+no_connect"))
    )
    (net (code "76") (name "unconnected-(U103-GPIO8-Pad11)") (class "Default")
      (node (ref "U103") (pin "11") (pinfunction "GPIO8_11") (pintype "bidirectional+no_connect"))
    )
    (net (code "77") (name "unconnected-(U103-GPIO9-Pad12)") (class "Default")
      (node (ref "U103") (pin "12") (pinfunction "GPIO9_12") (pintype "bidirectional+no_connect"))
    )
    (net (code "78") (name "unconnected-(U103-GPIO10-Pad13)") (class "Default")
      (node (ref "U103") (pin "13") (pinfunction "GPIO10_13") (pintype "bidirectional+no_connect"))
    )
    (net (code "79") (name "unconnected-(U103-GPIO11-Pad14)") (class "Default")
      (node (ref "U103") (pin "14") (pinfunction "GPIO11_14") (pintype "bidirectional+no_connect"))
    )
    (net (code "80") (name "unconnected-(U103-GPIO12-Pad15)") (class "Default")
      (node (ref "U103") (pin "15") (pinfunction "GPIO12_15") (pintype "bidirectional+no_connect"))
    )
    (net (code "81") (name "unconnected-(U103-GPIO13-Pad16)") (class "Default")
      (node (ref "U103") (pin "16") (pinfunction "GPIO13_16") (pintype "bidirectional+no_connect"))
    )
    (net (code "82") (name "unconnected-(U103-GPIO14-Pad17)") (class "Default")
      (node (ref "U103") (pin "17") (pinfunction "GPIO14_17") (pintype "bidirectional+no_connect"))
    )
    (net (code "83") (name "unconnected-(U103-GPIO15-Pad18)") (class "Default")
      (node (ref "U103") (pin "18") (pinfunction "GPIO15_18") (pintype "bidirectional+no_connect"))
    )
    (net (code "84") (name "unconnected-(U103-GPIO16-Pad27)") (class "Default")
      (node (ref "U103") (pin "27") (pinfunction "GPIO16_27") (pintype "bidirectional+no_connect"))
    )
    (net (code "85") (name "unconnected-(U103-GPIO17-Pad28)") (class "Default")
      (node (ref "U103") (pin "28") (pinfunction "GPIO17_28") (pintype "bidirectional+no_connect"))
    )
    (net (code "86") (name "unconnected-(U103-GPIO18-Pad29)") (class "Default")
      (node (ref "U103") (pin "29") (pinfunction "GPIO18_29") (pintype "bidirectional+no_connect"))
    )
    (net (code "87") (name "unconnected-(U103-GPIO19-Pad30)") (class "Default")
      (node (ref "U103") (pin "30") (pinfunction "GPIO19_30") (pintype "bidirectional+no_connect"))
    )
    (net (code "88") (name "unconnected-(U103-GPIO20-Pad31)") (class "Default")
      (node (ref "U103") (pin "31") (pinfunction "GPIO20_31") (pintype "bidirectional+no_connect"))
    )
    (net (code "89") (name "unconnected-(U103-GPIO21-Pad32)") (class "Default")
      (node (ref "U103") (pin "32") (pinfunction "GPIO21_32") (pintype "bidirectional+no_connect"))
    )
    (net (code "90") (name "unconnected-(U103-GPIO22-Pad34)") (class "Default")
      (node (ref "U103") (pin "34") (pinfunction "GPIO22_34") (pintype "bidirectional+no_connect"))
    )
    (net (code "91") (name "unconnected-(U103-GPIO29_ADC3-Pad41)") (class "Default")
      (node (ref "U103") (pin "41") (pinfunction "GPIO29_ADC3_41") (pintype "bidirectional+no_connect"))
    )
    (net (code "92") (name "unconnected-(U103-RUN-Pad26)") (class "Default")
      (node (ref "U103") (pin "26") (pinfunction "RUN_26") (pintype "input+no_connect"))
    )
    (net (code "93") (name "unconnected-(U103-SWCLK-Pad24)") (class "Default")
      (node (ref "U103") (pin "24") (pinfunction "SWCLK_24") (pintype "output+no_connect"))
    )
    (net (code "94") (name "unconnected-(U103-SWD-Pad25)") (class "Default")
      (node (ref "U103") (pin "25") (pinfunction "SWD_25") (pintype "bidirectional+no_connect"))
    )
    (net (code "95") (name "unconnected-(USB102-ID-Pad4)") (class "Default")
      (node (ref "USB102") (pin "4") (pinfunction "ID_4") (pintype "unspecified+no_connect"))
    )
  )
)
